# TinyRX4.net
KiCad netlist of a schematic drawn in EAGLE
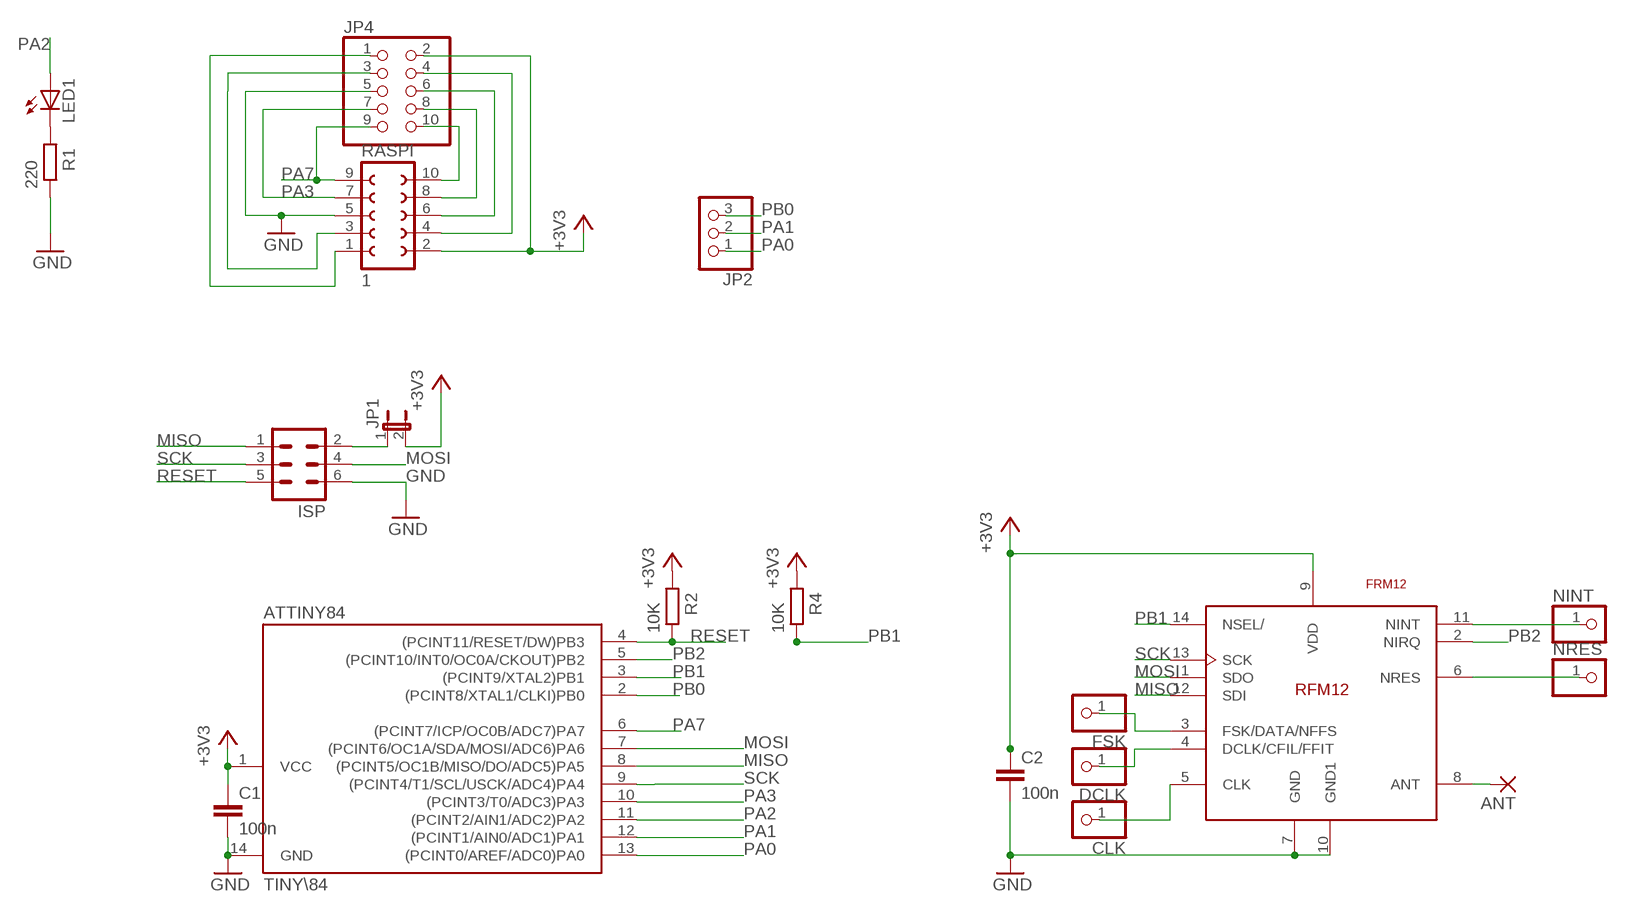
[diagram p0: schematic, sheet 1]

(export (version "E")
  (design (tool "Eeschema 10.0.6"))
  (components
    (comp (ref "ANT")
      (value "1,6/0,8")
      (footprint "eagle-import:1,6_0,8")
      (libsource (lib "eagle-import") (part "1,6/0,8"))
    )
    (comp (ref "ATTINY84")
      (value "TINY\\84")
      (footprint "eagle-import:SOIC14")
      (libsource (lib "eagle-import") (part "TINY24/44/84-SSU"))
    )
    (comp (ref "C1")
      (value "100n")
      (footprint "eagle-import:C0805")
      (libsource (lib "eagle-import") (part "C-EUC0805"))
    )
    (comp (ref "C2")
      (value "100n")
      (footprint "eagle-import:C0805")
      (libsource (lib "eagle-import") (part "C-EUC0805"))
    )
    (comp (ref "CLK")
      (value "PINHD-1X1")
      (footprint "eagle-import:1X01")
      (libsource (lib "eagle-import") (part "PINHD-1X1"))
    )
    (comp (ref "DCLK")
      (value "PINHD-1X1")
      (footprint "eagle-import:1X01")
      (libsource (lib "eagle-import") (part "PINHD-1X1"))
    )
    (comp (ref "FSK")
      (value "PINHD-1X1")
      (footprint "eagle-import:1X01")
      (libsource (lib "eagle-import") (part "PINHD-1X1"))
    )
    (comp (ref "ISP")
      (value "ML6")
      (footprint "eagle-import:ML6")
      (libsource (lib "eagle-import") (part "ML6"))
    )
    (comp (ref "JP1")
      (value "JUMPER-2PTH")
      (footprint "eagle-import:1X02")
      (libsource (lib "eagle-import") (part "JUMPER-2PTH"))
    )
    (comp (ref "JP2")
      (value "PINHD-1X3")
      (footprint "eagle-import:1X03")
      (libsource (lib "eagle-import") (part "PINHD-1X3"))
    )
    (comp (ref "JP4")
      (value "PINHD-2X5")
      (footprint "eagle-import:2X05")
      (libsource (lib "eagle-import") (part "PINHD-2X5"))
    )
    (comp (ref "LED1")
      (value "LEDSML0805")
      (footprint "eagle-import:SML0805")
      (libsource (lib "eagle-import") (part "LEDSML0805"))
    )
    (comp (ref "NINT")
      (value "PINHD-1X1")
      (footprint "eagle-import:1X01")
      (libsource (lib "eagle-import") (part "PINHD-1X1"))
    )
    (comp (ref "NRES")
      (value "PINHD-1X1")
      (footprint "eagle-import:1X01")
      (libsource (lib "eagle-import") (part "PINHD-1X1"))
    )
    (comp (ref "R1")
      (value "220")
      (footprint "eagle-import:R0805")
      (libsource (lib "eagle-import") (part "R-EU_R0805"))
    )
    (comp (ref "R2")
      (value "10K")
      (footprint "eagle-import:R0805")
      (libsource (lib "eagle-import") (part "R-EU_R0805"))
    )
    (comp (ref "R4")
      (value "10K")
      (footprint "eagle-import:R0805")
      (libsource (lib "eagle-import") (part "R-EU_R0805"))
    )
    (comp (ref "RASPI")
      (value "1")
      (footprint "eagle-import:FE05-2")
      (libsource (lib "eagle-import") (part "FE05-2"))
    )
    (comp (ref "U$1")
      (value "FRM12")
      (footprint "eagle-import:RFM12")
      (libsource (lib "eagle-import") (part "FRM12"))
    )
  )
  (nets
    (net (code "1") (name "+3V3") (class "Default")
      (node (ref "ATTINY84") (pin "1") (pinfunction "VCC_1") (pintype "power_in"))
      (node (ref "C1") (pin "1") (pinfunction "1_1") (pintype "passive"))
      (node (ref "C2") (pin "1") (pinfunction "1_1") (pintype "passive"))
      (node (ref "JP1") (pin "2") (pinfunction "2_2") (pintype "passive"))
      (node (ref "JP4") (pin "2") (pinfunction "2_2") (pintype "passive"))
      (node (ref "R2") (pin "2") (pinfunction "2_2") (pintype "passive"))
      (node (ref "R4") (pin "2") (pinfunction "2_2") (pintype "passive"))
      (node (ref "RASPI") (pin "2") (pinfunction "2_2") (pintype "passive"))
      (node (ref "U$1") (pin "9") (pinfunction "VDD_9") (pintype "power_in"))
    )
    (net (code "2") (name "/MISO") (class "Default")
      (node (ref "ATTINY84") (pin "8") (pinfunction "(PCINT5/OC1B/MISO/DO/ADC5)PA5_8") (pintype "bidirectional"))
      (node (ref "ISP") (pin "1") (pinfunction "1_1") (pintype "passive"))
      (node (ref "U$1") (pin "12") (pinfunction "SDI_12") (pintype "input"))
    )
    (net (code "3") (name "/MOSI") (class "Default")
      (node (ref "ATTINY84") (pin "7") (pinfunction "(PCINT6/OC1A/SDA/MOSI/ADC6)PA6_7") (pintype "bidirectional"))
      (node (ref "ISP") (pin "4") (pinfunction "4_4") (pintype "passive"))
      (node (ref "U$1") (pin "1") (pinfunction "SDO_1") (pintype "output"))
    )
    (net (code "4") (name "/PA0") (class "Default")
      (node (ref "ATTINY84") (pin "13") (pinfunction "(PCINT0/AREF/ADC0)PA0_13") (pintype "bidirectional"))
      (node (ref "JP2") (pin "1") (pinfunction "1_1") (pintype "passive"))
    )
    (net (code "5") (name "/PA1") (class "Default")
      (node (ref "ATTINY84") (pin "12") (pinfunction "(PCINT1/AIN0/ADC1)PA1_12") (pintype "bidirectional"))
      (node (ref "JP2") (pin "2") (pinfunction "2_2") (pintype "passive"))
    )
    (net (code "6") (name "/PA2") (class "Default")
      (node (ref "ATTINY84") (pin "11") (pinfunction "(PCINT2/AIN1/ADC2)PA2_11") (pintype "bidirectional"))
      (node (ref "LED1") (pin "A") (pinfunction "A_A") (pintype "passive"))
    )
    (net (code "7") (name "/PA3") (class "Default")
      (node (ref "ATTINY84") (pin "10") (pinfunction "(PCINT3/T0/ADC3)PA3_10") (pintype "bidirectional"))
      (node (ref "JP4") (pin "7") (pinfunction "7_7") (pintype "passive"))
      (node (ref "RASPI") (pin "7") (pinfunction "7_7") (pintype "passive"))
    )
    (net (code "8") (name "/PA7") (class "Default")
      (node (ref "ATTINY84") (pin "6") (pinfunction "(PCINT7/ICP/OC0B/ADC7)PA7_6") (pintype "bidirectional"))
      (node (ref "JP4") (pin "9") (pinfunction "9_9") (pintype "passive"))
      (node (ref "RASPI") (pin "9") (pinfunction "9_9") (pintype "passive"))
    )
    (net (code "9") (name "/PB0") (class "Default")
      (node (ref "ATTINY84") (pin "2") (pinfunction "(PCINT8/XTAL1/CLKI)PB0_2") (pintype "bidirectional"))
      (node (ref "JP2") (pin "3") (pinfunction "3_3") (pintype "passive"))
    )
    (net (code "10") (name "/PB1") (class "Default")
      (node (ref "ATTINY84") (pin "3") (pinfunction "(PCINT9/XTAL2)PB1_3") (pintype "bidirectional"))
      (node (ref "R4") (pin "1") (pinfunction "1_1") (pintype "passive"))
      (node (ref "U$1") (pin "14") (pinfunction "NSEL/_14") (pintype "input"))
    )
    (net (code "11") (name "/PB2") (class "Default")
      (node (ref "ATTINY84") (pin "5") (pinfunction "(PCINT10/INT0/OC0A/CKOUT)PB2_5") (pintype "bidirectional"))
      (node (ref "U$1") (pin "2") (pinfunction "NIRQ_2") (pintype "output"))
    )
    (net (code "12") (name "/RESET") (class "Default")
      (node (ref "ATTINY84") (pin "4") (pinfunction "(PCINT11/RESET/DW)PB3_4") (pintype "bidirectional"))
      (node (ref "ISP") (pin "5") (pinfunction "5_5") (pintype "passive"))
      (node (ref "R2") (pin "1") (pinfunction "1_1") (pintype "passive"))
    )
    (net (code "13") (name "/SCK") (class "Default")
      (node (ref "ATTINY84") (pin "9") (pinfunction "(PCINT4/T1/SCL/USCK/ADC4)PA4_9") (pintype "bidirectional"))
      (node (ref "ISP") (pin "3") (pinfunction "3_3") (pintype "passive"))
      (node (ref "U$1") (pin "13") (pinfunction "SCK_13") (pintype "input"))
    )
    (net (code "14") (name "GND") (class "Default")
      (node (ref "ATTINY84") (pin "14") (pinfunction "GND_14") (pintype "power_in"))
      (node (ref "C1") (pin "2") (pinfunction "2_2") (pintype "passive"))
      (node (ref "C2") (pin "2") (pinfunction "2_2") (pintype "passive"))
      (node (ref "ISP") (pin "6") (pinfunction "6_6") (pintype "passive"))
      (node (ref "JP4") (pin "5") (pinfunction "5_5") (pintype "passive"))
      (node (ref "R1") (pin "1") (pinfunction "1_1") (pintype "passive"))
      (node (ref "RASPI") (pin "5") (pinfunction "5_5") (pintype "passive"))
      (node (ref "U$1") (pin "10") (pinfunction "GND1_10") (pintype "passive"))
      (node (ref "U$1") (pin "7") (pinfunction "GND_7") (pintype "passive"))
    )
    (net (code "15") (name "Net-(ANT-P)") (class "Default")
      (node (ref "ANT") (pin "1") (pinfunction "P_1") (pintype "passive"))
      (node (ref "U$1") (pin "8") (pinfunction "ANT_8") (pintype "bidirectional"))
    )
    (net (code "16") (name "Net-(ISP-Pad2)") (class "Default")
      (node (ref "ISP") (pin "2") (pinfunction "2_2") (pintype "passive"))
      (node (ref "JP1") (pin "1") (pinfunction "1_1") (pintype "passive"))
    )
    (net (code "17") (name "Net-(JP4-Pad1)") (class "Default")
      (node (ref "JP4") (pin "1") (pinfunction "1_1") (pintype "passive"))
      (node (ref "RASPI") (pin "1") (pinfunction "1_1") (pintype "passive"))
    )
    (net (code "18") (name "Net-(JP4-Pad3)") (class "Default")
      (node (ref "JP4") (pin "3") (pinfunction "3_3") (pintype "passive"))
      (node (ref "RASPI") (pin "3") (pinfunction "3_3") (pintype "passive"))
    )
    (net (code "19") (name "Net-(JP4-Pad4)") (class "Default")
      (node (ref "JP4") (pin "4") (pinfunction "4_4") (pintype "passive"))
      (node (ref "RASPI") (pin "4") (pinfunction "4_4") (pintype "passive"))
    )
    (net (code "20") (name "Net-(JP4-Pad6)") (class "Default")
      (node (ref "JP4") (pin "6") (pinfunction "6_6") (pintype "passive"))
      (node (ref "RASPI") (pin "6") (pinfunction "6_6") (pintype "passive"))
    )
    (net (code "21") (name "Net-(JP4-Pad8)") (class "Default")
      (node (ref "JP4") (pin "8") (pinfunction "8_8") (pintype "passive"))
      (node (ref "RASPI") (pin "8") (pinfunction "8_8") (pintype "passive"))
    )
    (net (code "22") (name "Net-(JP4-Pad10)") (class "Default")
      (node (ref "JP4") (pin "10") (pinfunction "10_10") (pintype "passive"))
      (node (ref "RASPI") (pin "10") (pinfunction "10_10") (pintype "passive"))
    )
    (net (code "23") (name "Net-(LED1-PadC)") (class "Default")
      (node (ref "LED1") (pin "C") (pinfunction "C_C") (pintype "passive"))
      (node (ref "R1") (pin "2") (pinfunction "2_2") (pintype "passive"))
    )
    (net (code "24") (name "Net-(U$1-CLK)") (class "Default")
      (node (ref "CLK") (pin "1") (pinfunction "1_1") (pintype "passive"))
      (node (ref "U$1") (pin "5") (pinfunction "CLK_5") (pintype "output"))
    )
    (net (code "25") (name "Net-(U$1-DCLK{slash}CFIL{slash}FFIT)") (class "Default")
      (node (ref "DCLK") (pin "1") (pinfunction "1_1") (pintype "passive"))
      (node (ref "U$1") (pin "4") (pinfunction "DCLK/CFIL/FFIT_4") (pintype "bidirectional"))
    )
    (net (code "26") (name "Net-(U$1-FSK{slash}DATA{slash}NFFS)") (class "Default")
      (node (ref "FSK") (pin "1") (pinfunction "1_1") (pintype "passive"))
      (node (ref "U$1") (pin "3") (pinfunction "FSK/DATA/NFFS_3") (pintype "bidirectional"))
    )
    (net (code "27") (name "Net-(U$1-NINT)") (class "Default")
      (node (ref "NINT") (pin "1") (pinfunction "1_1") (pintype "passive"))
      (node (ref "U$1") (pin "11") (pinfunction "NINT_11") (pintype "bidirectional"))
    )
    (net (code "28") (name "Net-(U$1-NRES)") (class "Default")
      (node (ref "NRES") (pin "1") (pinfunction "1_1") (pintype "passive"))
      (node (ref "U$1") (pin "6") (pinfunction "NRES_6") (pintype "bidirectional"))
    )
  )
)
